# Interface.net
KiCad netlist of a schematic drawn in Altium Designer
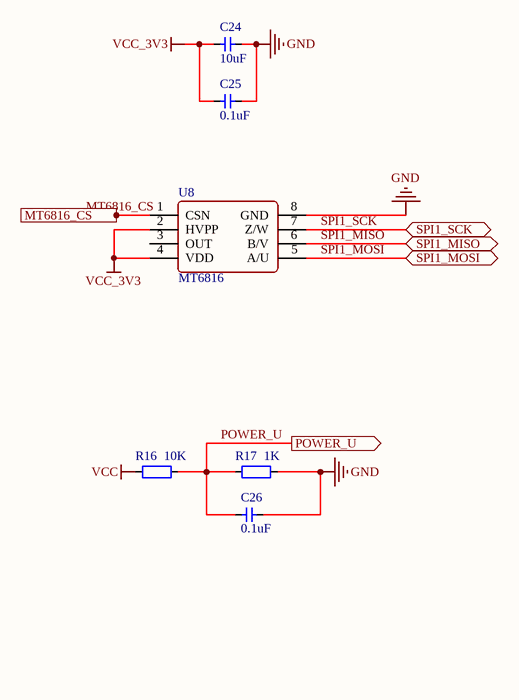
[diagram p0: Interface.SchDoc]

(export (version "E")
  (design (tool "Eeschema 10.0.6"))
  (components
    (comp (ref "C24")
      (value "10uF")
      (footprint "CAP_0402")
      (description "Capacitor")
      (libsource (lib "MyPcbLib") (part "电容-0402"))
    )
    (comp (ref "C25")
      (value "0.1uF")
      (footprint "motor42-lib:CAP_0402")
      (description "Capacitor")
      (libsource (lib "MyPcbLib") (part "电容-0402"))
    )
    (comp (ref "C26")
      (value "0.1uF")
      (footprint "motor42-lib:CAP_0402")
      (description "Capacitor")
      (libsource (lib "MyPcbLib") (part "电容-0402"))
    )
    (comp (ref "R16")
      (value "10K")
      (footprint "RES_0402")
      (description "Resistor")
      (libsource (lib "MyPcbLib") (part "电阻-0402"))
    )
    (comp (ref "R17")
      (value "1K")
      (footprint "RES_0402")
      (description "Resistor")
      (libsource (lib "MyPcbLib") (part "电阻-0402"))
    )
    (comp (ref "U8")
      (value "MT6816")
      (footprint "SO-8")
      (description "Magnetic Position Sensor")
      (libsource (lib "MyPcbLib") (part "MT6816"))
    )
  )
  (nets
    (net (code "1") (name "/MT6816_CS") (class "Default")
      (node (ref "U8") (pin "1") (pinfunction "CSN_1") (pintype "passive"))
    )
    (net (code "2") (name "/POWER_U") (class "Default")
      (node (ref "C26") (pin "2") (pinfunction "2_2") (pintype "passive"))
      (node (ref "R16") (pin "2") (pinfunction "2_2") (pintype "passive"))
      (node (ref "R17") (pin "1") (pinfunction "1_1") (pintype "passive"))
    )
    (net (code "3") (name "/SPI1_MISO") (class "Default")
      (node (ref "U8") (pin "6") (pinfunction "B/V_6") (pintype "passive"))
    )
    (net (code "4") (name "/SPI1_MOSI") (class "Default")
      (node (ref "U8") (pin "5") (pinfunction "A/U_5") (pintype "passive"))
    )
    (net (code "5") (name "/SPI1_SCK") (class "Default")
      (node (ref "U8") (pin "7") (pinfunction "Z/W_7") (pintype "passive"))
    )
    (net (code "6") (name "GND") (class "Default")
      (node (ref "C24") (pin "1") (pinfunction "1_1") (pintype "passive"))
      (node (ref "C25") (pin "1") (pinfunction "1_1") (pintype "passive"))
      (node (ref "C26") (pin "1") (pinfunction "1_1") (pintype "passive"))
      (node (ref "R17") (pin "2") (pinfunction "2_2") (pintype "passive"))
      (node (ref "U8") (pin "8") (pinfunction "GND_8") (pintype "passive"))
    )
    (net (code "7") (name "VCC") (class "Default")
      (node (ref "R16") (pin "1") (pinfunction "1_1") (pintype "passive"))
    )
    (net (code "8") (name "VCC_3V3") (class "Default")
      (node (ref "C24") (pin "2") (pinfunction "2_2") (pintype "passive"))
      (node (ref "C25") (pin "2") (pinfunction "2_2") (pintype "passive"))
      (node (ref "U8") (pin "2") (pinfunction "HVPP_2") (pintype "passive"))
      (node (ref "U8") (pin "4") (pinfunction "VDD_4") (pintype "passive"))
    )
    (net (code "9") (name "unconnected-(U8-OUT-Pad3)") (class "Default")
      (node (ref "U8") (pin "3") (pinfunction "OUT_3") (pintype "passive"))
    )
  )
)
